# 2-channels-audio-amp.net
KiCad netlist of a schematic drawn in EAGLE
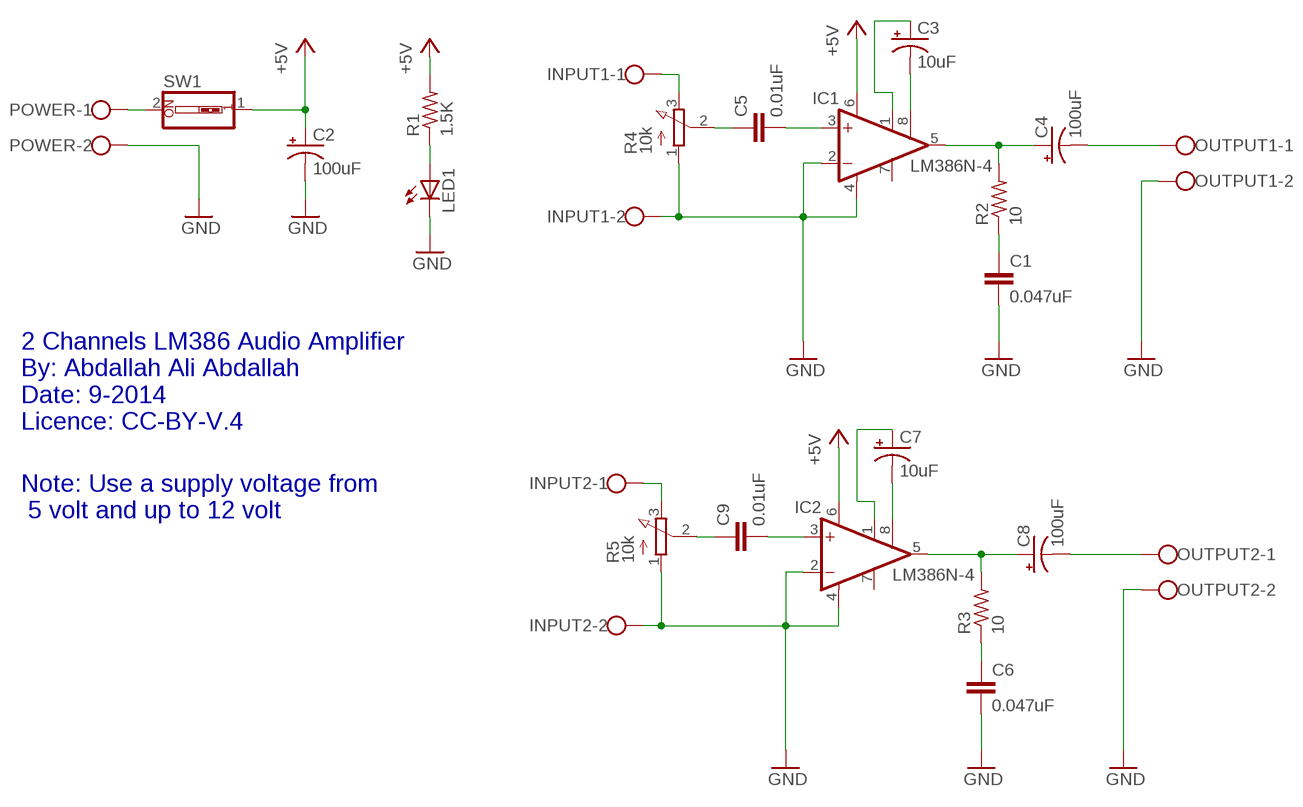
[diagram p0: schematic, sheet 1]

(export (version "E")
  (design (tool "Eeschema 10.0.6"))
  (components
    (comp (ref "C1")
      (value "0.047uF")
      (footprint "eagle-import:C025-025X050")
      (libsource (lib "eagle-import") (part "C-EU025-025X050"))
    )
    (comp (ref "C2")
      (value "100uF")
      (footprint "eagle-import:E2,5-6")
      (libsource (lib "eagle-import") (part "CPOL-USE2.5-6"))
    )
    (comp (ref "C3")
      (value "10uF")
      (footprint "eagle-import:E2,5-6")
      (libsource (lib "eagle-import") (part "CPOL-USE2.5-6"))
    )
    (comp (ref "C4")
      (value "100uF")
      (footprint "eagle-import:E2,5-6")
      (libsource (lib "eagle-import") (part "CPOL-USE2.5-6"))
    )
    (comp (ref "C5")
      (value "0.01uF")
      (footprint "eagle-import:C025-025X050")
      (libsource (lib "eagle-import") (part "C-EU025-025X050"))
    )
    (comp (ref "C6")
      (value "0.047uF")
      (footprint "eagle-import:C025-025X050")
      (libsource (lib "eagle-import") (part "C-EU025-025X050"))
    )
    (comp (ref "C7")
      (value "10uF")
      (footprint "eagle-import:E2,5-6")
      (libsource (lib "eagle-import") (part "CPOL-USE2.5-6"))
    )
    (comp (ref "C8")
      (value "100uF")
      (footprint "eagle-import:E2,5-6")
      (libsource (lib "eagle-import") (part "CPOL-USE2.5-6"))
    )
    (comp (ref "C9")
      (value "0.01uF")
      (footprint "eagle-import:C025-025X050")
      (libsource (lib "eagle-import") (part "C-EU025-025X050"))
    )
    (comp (ref "IC1")
      (value "LM386N-4")
      (footprint "eagle-import:DIL08")
      (libsource (lib "eagle-import") (part "LM386?-N4"))
    )
    (comp (ref "IC2")
      (value "LM386N-4")
      (footprint "eagle-import:DIL08")
      (libsource (lib "eagle-import") (part "LM386?-N4"))
    )
    (comp (ref "INPUT1")
      (value "W237-102")
      (footprint "eagle-import:W237-102")
      (fields (field (name "MPN") "237-102"))
      (libsource (lib "eagle-import") (part "W237-102"))
    )
    (comp (ref "INPUT2")
      (value "W237-102")
      (footprint "eagle-import:W237-102")
      (fields (field (name "MPN") "237-102"))
      (libsource (lib "eagle-import") (part "W237-102"))
    )
    (comp (ref "LED1")
      (value "LED5MM")
      (footprint "eagle-import:LED5MM")
      (libsource (lib "eagle-import") (part "LED5MM"))
    )
    (comp (ref "OUTPUT1")
      (value "W237-102")
      (footprint "eagle-import:W237-102")
      (fields (field (name "MPN") "237-102"))
      (libsource (lib "eagle-import") (part "W237-102"))
    )
    (comp (ref "OUTPUT2")
      (value "W237-102")
      (footprint "eagle-import:W237-102")
      (fields (field (name "MPN") "237-102"))
      (libsource (lib "eagle-import") (part "W237-102"))
    )
    (comp (ref "POWER")
      (value "W237-102")
      (footprint "eagle-import:W237-102")
      (fields (field (name "MPN") "237-102"))
      (libsource (lib "eagle-import") (part "W237-102"))
    )
    (comp (ref "R1")
      (value "1.5K")
      (footprint "eagle-import:0204_7")
      (libsource (lib "eagle-import") (part "R-US_0204/7"))
    )
    (comp (ref "R2")
      (value "10")
      (footprint "eagle-import:0204_7")
      (libsource (lib "eagle-import") (part "R-US_0204/7"))
    )
    (comp (ref "R3")
      (value "10")
      (footprint "eagle-import:0204_7")
      (libsource (lib "eagle-import") (part "R-US_0204/7"))
    )
    (comp (ref "R4")
      (value "10k")
      (footprint "eagle-import:3RP_1610N")
      (libsource (lib "eagle-import") (part "3RP/1610N"))
    )
    (comp (ref "R5")
      (value "10k")
      (footprint "eagle-import:3RP_1610N")
      (libsource (lib "eagle-import") (part "3RP/1610N"))
    )
    (comp (ref "SW1")
      (value "SW_DIP-1")
      (footprint "eagle-import:EDG-01")
      (libsource (lib "eagle-import") (part "SW_DIP-1"))
    )
  )
  (nets
    (net (code "1") (name "+5V") (class "Default")
      (node (ref "C2") (pin "+") (pinfunction "+_+") (pintype "passive"))
      (node (ref "IC1") (pin "6") (pinfunction "VS_6") (pintype "power_in"))
      (node (ref "IC2") (pin "6") (pinfunction "VS_6") (pintype "power_in"))
      (node (ref "R1") (pin "2") (pinfunction "2_2") (pintype "passive"))
      (node (ref "SW1") (pin "1") (pinfunction "1_1") (pintype "passive"))
    )
    (net (code "2") (name "GND") (class "Default")
      (node (ref "C1") (pin "2") (pinfunction "2_2") (pintype "passive"))
      (node (ref "C2") (pin "-") (pinfunction "-_-") (pintype "passive"))
      (node (ref "C6") (pin "2") (pinfunction "2_2") (pintype "passive"))
      (node (ref "IC1") (pin "2") (pinfunction "-IN_2") (pintype "input"))
      (node (ref "IC1") (pin "4") (pinfunction "GND_4") (pintype "power_in"))
      (node (ref "IC2") (pin "2") (pinfunction "-IN_2") (pintype "input"))
      (node (ref "IC2") (pin "4") (pinfunction "GND_4") (pintype "power_in"))
      (node (ref "INPUT1") (pin "2") (pinfunction "KL_2") (pintype "passive"))
      (node (ref "INPUT2") (pin "2") (pinfunction "KL_2") (pintype "passive"))
      (node (ref "LED1") (pin "K") (pinfunction "C_K") (pintype "passive"))
      (node (ref "OUTPUT1") (pin "2") (pinfunction "KL_2") (pintype "passive"))
      (node (ref "OUTPUT2") (pin "2") (pinfunction "KL_2") (pintype "passive"))
      (node (ref "POWER") (pin "2") (pinfunction "KL_2") (pintype "passive"))
      (node (ref "R4") (pin "1") (pinfunction "A_1") (pintype "passive"))
      (node (ref "R5") (pin "1") (pinfunction "A_1") (pintype "passive"))
    )
    (net (code "3") (name "Net-(C1-Pad1)") (class "Default")
      (node (ref "C1") (pin "1") (pinfunction "1_1") (pintype "passive"))
      (node (ref "R2") (pin "1") (pinfunction "1_1") (pintype "passive"))
    )
    (net (code "4") (name "Net-(C3-Pad+)") (class "Default")
      (node (ref "C3") (pin "+") (pinfunction "+_+") (pintype "passive"))
      (node (ref "IC1") (pin "1") (pinfunction "GAIN_1") (pintype "passive"))
    )
    (net (code "5") (name "Net-(C3-Pad-)") (class "Default")
      (node (ref "C3") (pin "-") (pinfunction "-_-") (pintype "passive"))
      (node (ref "IC1") (pin "8") (pinfunction "GAIN_8") (pintype "passive"))
    )
    (net (code "6") (name "Net-(C6-Pad1)") (class "Default")
      (node (ref "C6") (pin "1") (pinfunction "1_1") (pintype "passive"))
      (node (ref "R3") (pin "1") (pinfunction "1_1") (pintype "passive"))
    )
    (net (code "7") (name "Net-(C7-Pad+)") (class "Default")
      (node (ref "C7") (pin "+") (pinfunction "+_+") (pintype "passive"))
      (node (ref "IC2") (pin "1") (pinfunction "GAIN_1") (pintype "passive"))
    )
    (net (code "8") (name "Net-(C7-Pad-)") (class "Default")
      (node (ref "C7") (pin "-") (pinfunction "-_-") (pintype "passive"))
      (node (ref "IC2") (pin "8") (pinfunction "GAIN_8") (pintype "passive"))
    )
    (net (code "9") (name "Net-(IC1-+IN)") (class "Default")
      (node (ref "C5") (pin "2") (pinfunction "2_2") (pintype "passive"))
      (node (ref "IC1") (pin "3") (pinfunction "+IN_3") (pintype "input"))
    )
    (net (code "10") (name "Net-(IC1-OUT)") (class "Default")
      (node (ref "C4") (pin "+") (pinfunction "+_+") (pintype "passive"))
      (node (ref "IC1") (pin "5") (pinfunction "OUT_5") (pintype "output"))
      (node (ref "R2") (pin "2") (pinfunction "2_2") (pintype "passive"))
    )
    (net (code "11") (name "Net-(IC2-+IN)") (class "Default")
      (node (ref "C9") (pin "2") (pinfunction "2_2") (pintype "passive"))
      (node (ref "IC2") (pin "3") (pinfunction "+IN_3") (pintype "input"))
    )
    (net (code "12") (name "Net-(IC2-OUT)") (class "Default")
      (node (ref "C8") (pin "+") (pinfunction "+_+") (pintype "passive"))
      (node (ref "IC2") (pin "5") (pinfunction "OUT_5") (pintype "output"))
      (node (ref "R3") (pin "2") (pinfunction "2_2") (pintype "passive"))
    )
    (net (code "13") (name "Net-(INPUT1A-KL)") (class "Default")
      (node (ref "INPUT1") (pin "1") (pinfunction "KL_1") (pintype "passive"))
      (node (ref "R4") (pin "3") (pinfunction "E_3") (pintype "passive"))
    )
    (net (code "14") (name "Net-(INPUT2A-KL)") (class "Default")
      (node (ref "INPUT2") (pin "1") (pinfunction "KL_1") (pintype "passive"))
      (node (ref "R5") (pin "3") (pinfunction "E_3") (pintype "passive"))
    )
    (net (code "15") (name "Net-(LED1-PadA)") (class "Default")
      (node (ref "LED1") (pin "A") (pinfunction "A_A") (pintype "passive"))
      (node (ref "R1") (pin "1") (pinfunction "1_1") (pintype "passive"))
    )
    (net (code "16") (name "Net-(OUTPUT1A-KL)") (class "Default")
      (node (ref "C4") (pin "-") (pinfunction "-_-") (pintype "passive"))
      (node (ref "OUTPUT1") (pin "1") (pinfunction "KL_1") (pintype "passive"))
    )
    (net (code "17") (name "Net-(OUTPUT2A-KL)") (class "Default")
      (node (ref "C8") (pin "-") (pinfunction "-_-") (pintype "passive"))
      (node (ref "OUTPUT2") (pin "1") (pinfunction "KL_1") (pintype "passive"))
    )
    (net (code "18") (name "Net-(POWERA-KL)") (class "Default")
      (node (ref "POWER") (pin "1") (pinfunction "KL_1") (pintype "passive"))
      (node (ref "SW1") (pin "2") (pinfunction "2_2") (pintype "passive"))
    )
    (net (code "19") (name "Net-(R4-S)") (class "Default")
      (node (ref "C5") (pin "1") (pinfunction "1_1") (pintype "passive"))
      (node (ref "R4") (pin "2") (pinfunction "S_2") (pintype "passive"))
    )
    (net (code "20") (name "Net-(R5-S)") (class "Default")
      (node (ref "C9") (pin "1") (pinfunction "1_1") (pintype "passive"))
      (node (ref "R5") (pin "2") (pinfunction "S_2") (pintype "passive"))
    )
    (net (code "21") (name "unconnected-(IC1-BYPASS-Pad7)") (class "Default")
      (node (ref "IC1") (pin "7") (pinfunction "BYPASS_7") (pintype "passive"))
    )
    (net (code "22") (name "unconnected-(IC2-BYPASS-Pad7)") (class "Default")
      (node (ref "IC2") (pin "7") (pinfunction "BYPASS_7") (pintype "passive"))
    )
  )
)
